# PCB-Extended.net
KiCad netlist of a schematic drawn in EAGLE
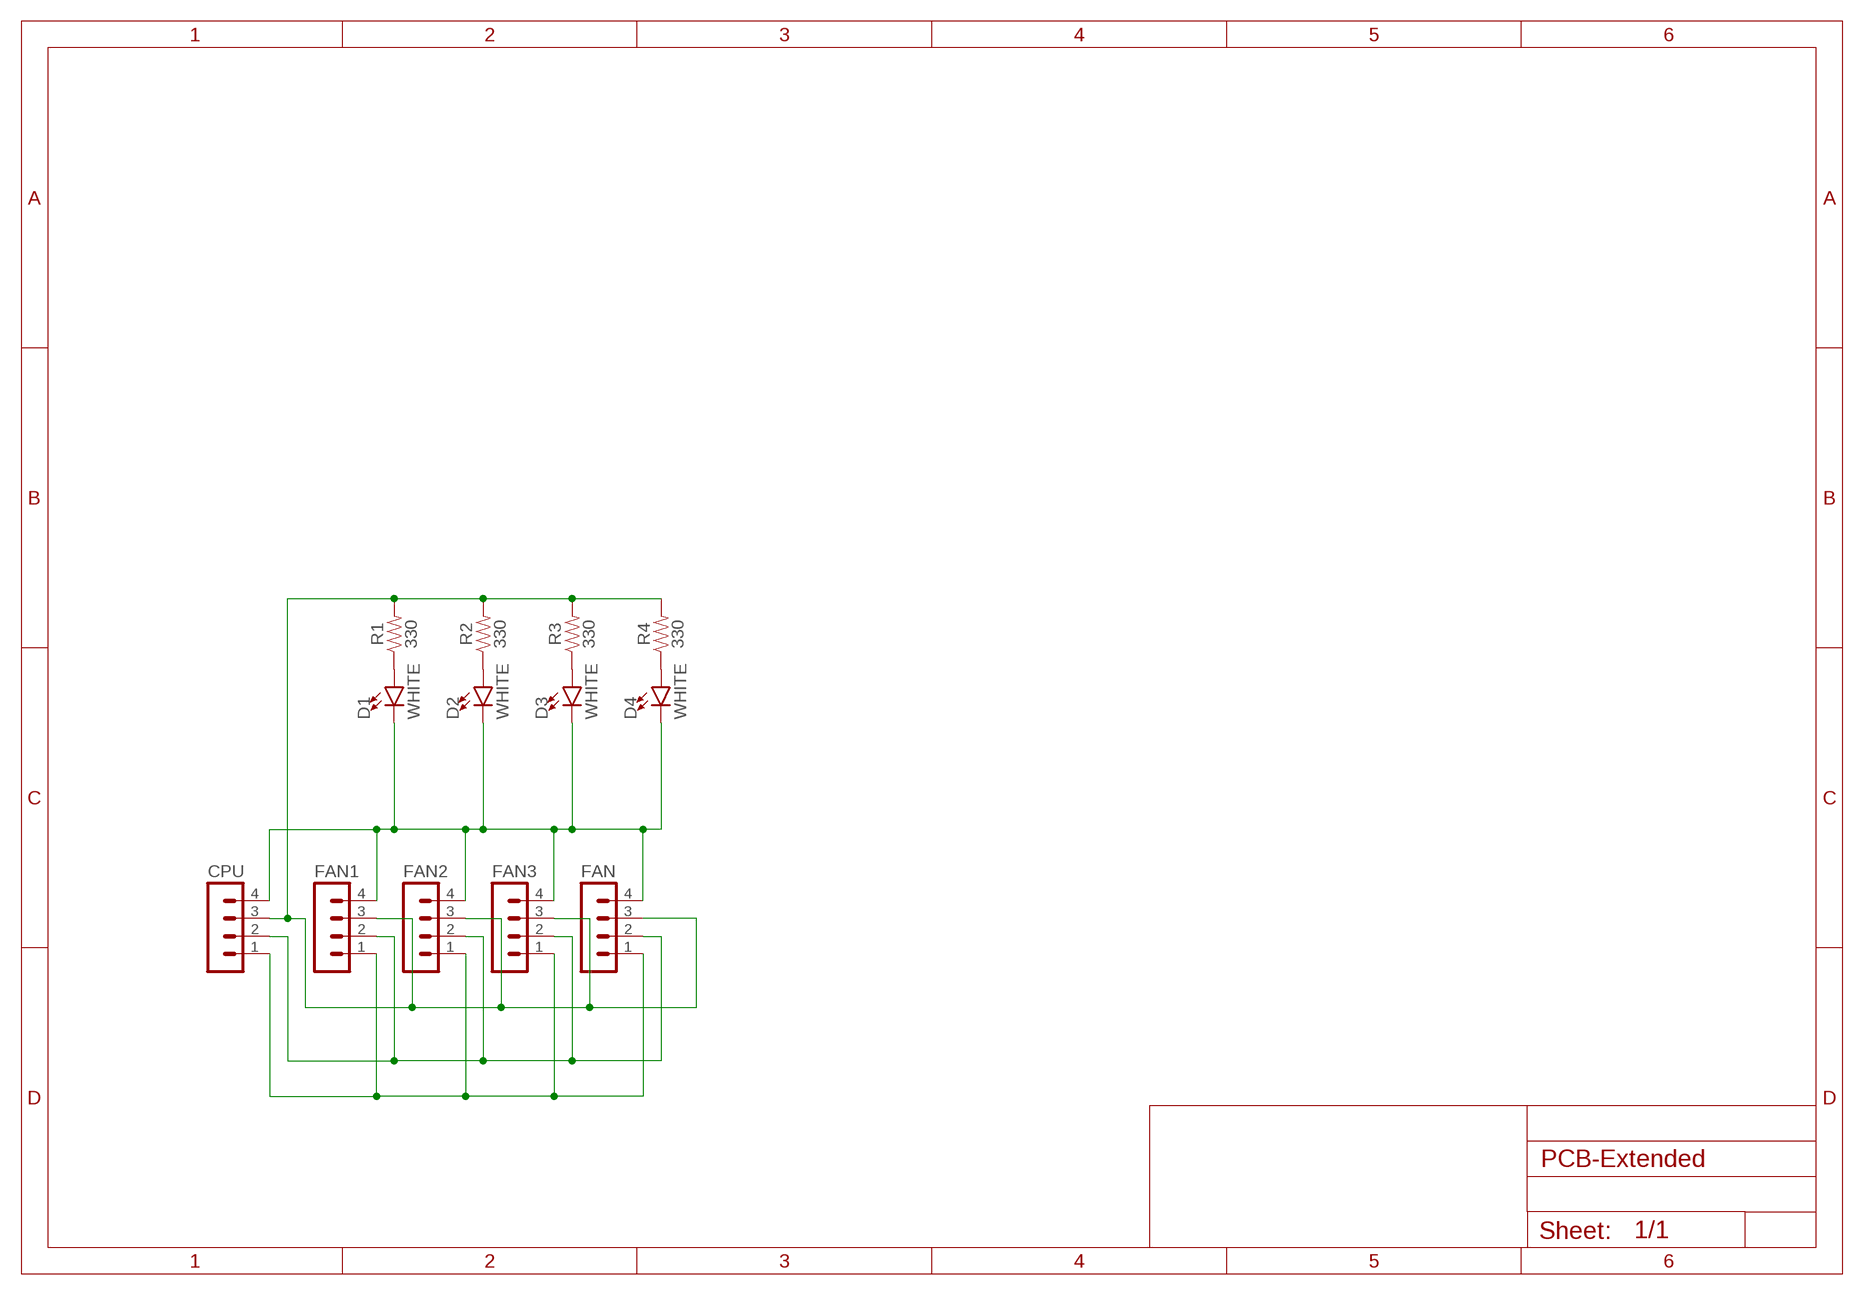
[diagram p0: schematic, sheet 1]

(export (version "E")
  (design (tool "Eeschema 10.0.6"))
  (components
    (comp (ref "CPU")
      (value "MA04-1")
      (footprint "eagle-import:MA04-1")
      (libsource (lib "eagle-import") (part "MA04-1"))
    )
    (comp (ref "D1")
      (value "WHITE")
      (footprint "eagle-import:LED-1206")
      (libsource (lib "eagle-import") (part "LED-WHITE1206"))
    )
    (comp (ref "D2")
      (value "WHITE")
      (footprint "eagle-import:LED-1206")
      (libsource (lib "eagle-import") (part "LED-WHITE1206"))
    )
    (comp (ref "D3")
      (value "WHITE")
      (footprint "eagle-import:LED-1206")
      (libsource (lib "eagle-import") (part "LED-WHITE1206"))
    )
    (comp (ref "D4")
      (value "WHITE")
      (footprint "eagle-import:LED-1206")
      (libsource (lib "eagle-import") (part "LED-WHITE1206"))
    )
    (comp (ref "FAN")
      (value "MA04-1")
      (footprint "eagle-import:MA04-1")
      (libsource (lib "eagle-import") (part "MA04-1"))
    )
    (comp (ref "FAN1")
      (value "MA04-1")
      (footprint "eagle-import:MA04-1")
      (libsource (lib "eagle-import") (part "MA04-1"))
    )
    (comp (ref "FAN2")
      (value "MA04-1")
      (footprint "eagle-import:MA04-1")
      (libsource (lib "eagle-import") (part "MA04-1"))
    )
    (comp (ref "FAN3")
      (value "MA04-1")
      (footprint "eagle-import:MA04-1")
      (libsource (lib "eagle-import") (part "MA04-1"))
    )
    (comp (ref "R1")
      (value "330")
      (footprint "eagle-import:0603")
      (libsource (lib "eagle-import") (part "0.27OHM-0603-1/10W-1%"))
    )
    (comp (ref "R2")
      (value "330")
      (footprint "eagle-import:0603")
      (libsource (lib "eagle-import") (part "0.27OHM-0603-1/10W-1%"))
    )
    (comp (ref "R3")
      (value "330")
      (footprint "eagle-import:0603")
      (libsource (lib "eagle-import") (part "0.27OHM-0603-1/10W-1%"))
    )
    (comp (ref "R4")
      (value "330")
      (footprint "eagle-import:0603")
      (libsource (lib "eagle-import") (part "0.27OHM-0603-1/10W-1%"))
    )
  )
  (nets
    (net (code "1") (name "Net-(CPU-Pad1)") (class "Default")
      (node (ref "CPU") (pin "1") (pinfunction "1_1") (pintype "passive"))
      (node (ref "FAN") (pin "1") (pinfunction "1_1") (pintype "passive"))
      (node (ref "FAN1") (pin "1") (pinfunction "1_1") (pintype "passive"))
      (node (ref "FAN2") (pin "1") (pinfunction "1_1") (pintype "passive"))
      (node (ref "FAN3") (pin "1") (pinfunction "1_1") (pintype "passive"))
    )
    (net (code "2") (name "Net-(CPU-Pad2)") (class "Default")
      (node (ref "CPU") (pin "2") (pinfunction "2_2") (pintype "passive"))
      (node (ref "FAN") (pin "2") (pinfunction "2_2") (pintype "passive"))
      (node (ref "FAN1") (pin "2") (pinfunction "2_2") (pintype "passive"))
      (node (ref "FAN2") (pin "2") (pinfunction "2_2") (pintype "passive"))
      (node (ref "FAN3") (pin "2") (pinfunction "2_2") (pintype "passive"))
    )
    (net (code "3") (name "Net-(CPU-Pad3)") (class "Default")
      (node (ref "CPU") (pin "3") (pinfunction "3_3") (pintype "passive"))
      (node (ref "FAN") (pin "3") (pinfunction "3_3") (pintype "passive"))
      (node (ref "FAN1") (pin "3") (pinfunction "3_3") (pintype "passive"))
      (node (ref "FAN2") (pin "3") (pinfunction "3_3") (pintype "passive"))
      (node (ref "FAN3") (pin "3") (pinfunction "3_3") (pintype "passive"))
      (node (ref "R1") (pin "2") (pinfunction "2_2") (pintype "passive"))
      (node (ref "R2") (pin "2") (pinfunction "2_2") (pintype "passive"))
      (node (ref "R3") (pin "2") (pinfunction "2_2") (pintype "passive"))
      (node (ref "R4") (pin "2") (pinfunction "2_2") (pintype "passive"))
    )
    (net (code "4") (name "Net-(CPU-Pad4)") (class "Default")
      (node (ref "CPU") (pin "4") (pinfunction "4_4") (pintype "passive"))
      (node (ref "D1") (pin "C") (pinfunction "C_C") (pintype "passive"))
      (node (ref "D2") (pin "C") (pinfunction "C_C") (pintype "passive"))
      (node (ref "D3") (pin "C") (pinfunction "C_C") (pintype "passive"))
      (node (ref "D4") (pin "C") (pinfunction "C_C") (pintype "passive"))
      (node (ref "FAN") (pin "4") (pinfunction "4_4") (pintype "passive"))
      (node (ref "FAN1") (pin "4") (pinfunction "4_4") (pintype "passive"))
      (node (ref "FAN2") (pin "4") (pinfunction "4_4") (pintype "passive"))
      (node (ref "FAN3") (pin "4") (pinfunction "4_4") (pintype "passive"))
    )
    (net (code "5") (name "Net-(D1-PadA)") (class "Default")
      (node (ref "D1") (pin "A") (pinfunction "A_A") (pintype "passive"))
      (node (ref "R1") (pin "1") (pinfunction "1_1") (pintype "passive"))
    )
    (net (code "6") (name "Net-(D2-PadA)") (class "Default")
      (node (ref "D2") (pin "A") (pinfunction "A_A") (pintype "passive"))
      (node (ref "R2") (pin "1") (pinfunction "1_1") (pintype "passive"))
    )
    (net (code "7") (name "Net-(D3-PadA)") (class "Default")
      (node (ref "D3") (pin "A") (pinfunction "A_A") (pintype "passive"))
      (node (ref "R3") (pin "1") (pinfunction "1_1") (pintype "passive"))
    )
    (net (code "8") (name "Net-(D4-PadA)") (class "Default")
      (node (ref "D4") (pin "A") (pinfunction "A_A") (pintype "passive"))
      (node (ref "R4") (pin "1") (pinfunction "1_1") (pintype "passive"))
    )
  )
)
